# 8mu_pub.net
KiCad netlist of a schematic drawn in EAGLE
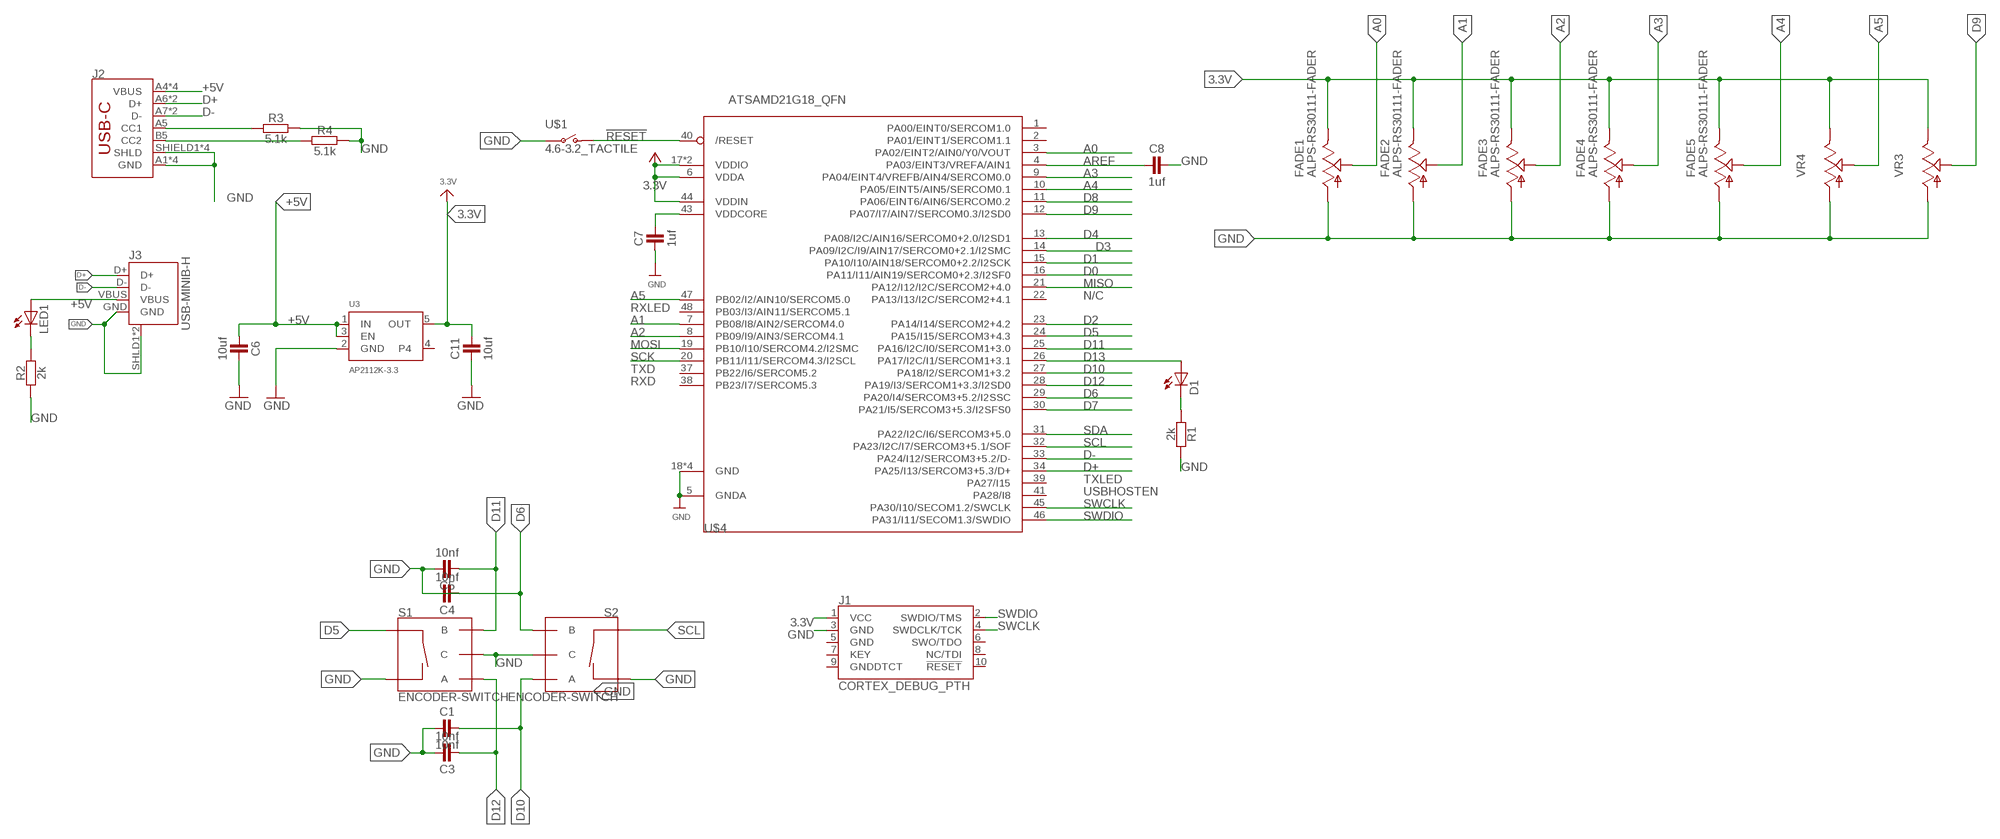
[diagram p0: schematic, sheet 1]

(export (version "E")
  (design (tool "Eeschema 10.0.6"))
  (components
    (comp (ref "C1")
      (value "10nf")
      (footprint "eagle-import:C0603")
      (libsource (lib "eagle-import") (part "CAPACITOR-0603"))
    )
    (comp (ref "C3")
      (value "10nf")
      (footprint "eagle-import:C0603")
      (libsource (lib "eagle-import") (part "CAPACITOR-0603"))
    )
    (comp (ref "C4")
      (value "10nf")
      (footprint "eagle-import:C0603")
      (libsource (lib "eagle-import") (part "CAPACITOR-0603"))
    )
    (comp (ref "C5")
      (value "10nf")
      (footprint "eagle-import:C0603")
      (libsource (lib "eagle-import") (part "CAPACITOR-0603"))
    )
    (comp (ref "C6")
      (value "10uf")
      (footprint "eagle-import:C0603")
      (libsource (lib "eagle-import") (part "CAPACITOR-0603"))
    )
    (comp (ref "C7")
      (value "1uf")
      (footprint "eagle-import:C0603")
      (libsource (lib "eagle-import") (part "CAPACITOR-0603"))
    )
    (comp (ref "C8")
      (value "1uf")
      (footprint "eagle-import:C0603")
      (libsource (lib "eagle-import") (part "CAPACITOR-0603"))
    )
    (comp (ref "C11")
      (value "10uf")
      (footprint "eagle-import:C0603")
      (libsource (lib "eagle-import") (part "CAPACITOR-0603"))
    )
    (comp (ref "D1")
      (value "LED3MM")
      (footprint "eagle-import:LED3MM")
      (libsource (lib "eagle-import") (part "LED3MM"))
    )
    (comp (ref "FADE1")
      (value "ALPS-RS30111-FADER")
      (footprint "eagle-import:ALPS-RS30111-FADER")
      (libsource (lib "eagle-import") (part "ALPS-RS30111-FADER"))
    )
    (comp (ref "FADE2")
      (value "ALPS-RS30111-FADER")
      (footprint "eagle-import:ALPS-RS30111-FADER")
      (libsource (lib "eagle-import") (part "ALPS-RS30111-FADER"))
    )
    (comp (ref "FADE3")
      (value "ALPS-RS30111-FADER")
      (footprint "eagle-import:ALPS-RS30111-FADER")
      (libsource (lib "eagle-import") (part "ALPS-RS30111-FADER"))
    )
    (comp (ref "FADE4")
      (value "ALPS-RS30111-FADER")
      (footprint "eagle-import:ALPS-RS30111-FADER")
      (libsource (lib "eagle-import") (part "ALPS-RS30111-FADER"))
    )
    (comp (ref "FADE5")
      (value "ALPS-RS30111-FADER")
      (footprint "eagle-import:ALPS-RS30111-FADER")
      (libsource (lib "eagle-import") (part "ALPS-RS30111-FADER"))
    )
    (comp (ref "J1")
      (value "CORTEX_DEBUG_PTH")
      (footprint "eagle-import:2X5-PTH-1.27MM")
      (libsource (lib "eagle-import") (part "CORTEX_DEBUG_PTH"))
    )
    (comp (ref "J2")
      (value "USB_C")
      (footprint "eagle-import:CX90M-16P-USB-C-MIDMOUNT")
      (libsource (lib "eagle-import") (part "USB_C"))
    )
    (comp (ref "J3")
      (value "USB-MINIB-H")
      (footprint "eagle-import:USB-MINIB-H")
      (libsource (lib "eagle-import") (part "USB-MINIB-H"))
    )
    (comp (ref "LED1")
      (value "LED3MM")
      (footprint "eagle-import:LED3MM")
      (libsource (lib "eagle-import") (part "LED3MM"))
    )
    (comp (ref "R1")
      (value "2k")
      (footprint "eagle-import:C0603")
      (libsource (lib "eagle-import") (part "RESISTOR-0603"))
    )
    (comp (ref "R2")
      (value "2k")
      (footprint "eagle-import:C0603")
      (libsource (lib "eagle-import") (part "RESISTOR-0603"))
    )
    (comp (ref "R3")
      (value "5.1k")
      (footprint "eagle-import:C0603")
      (libsource (lib "eagle-import") (part "RESISTOR-0603"))
    )
    (comp (ref "R4")
      (value "5.1k")
      (footprint "eagle-import:C0603")
      (libsource (lib "eagle-import") (part "RESISTOR-0603"))
    )
    (comp (ref "S1")
      (value "ENCODER-SWITCH")
      (footprint "eagle-import:ROTARY_ENC_PLAIN")
      (libsource (lib "eagle-import") (part "ENCODER-SWITCH"))
    )
    (comp (ref "S2")
      (value "ENCODER-SWITCH")
      (footprint "eagle-import:ROTARY_ENC_PLAIN")
      (libsource (lib "eagle-import") (part "ENCODER-SWITCH"))
    )
    (comp (ref "U$1")
      (value "4.6-3.2_TACTILE")
      (footprint "eagle-import:TACTILE_SWITCH_SMD_4.6X2.8MM")
      (libsource (lib "eagle-import") (part "4.6-3.2_TACTILE"))
    )
    (comp (ref "U$4")
      (value "ATSAMD21G18_QFN")
      (footprint "eagle-import:TQFN48_7MM")
      (libsource (lib "eagle-import") (part "ATSAMD21J_QFN"))
    )
    (comp (ref "U3")
      (value "AP2112K-3.3")
      (footprint "eagle-import:SOT23-5")
      (libsource (lib "eagle-import") (part "VREG_SOT23-5"))
    )
    (comp (ref "VR3")
      (value "9MM_SNAP-IN_POT_")
      (footprint "eagle-import:9MM_SNAP-IN_POT")
      (libsource (lib "eagle-import") (part "9MM_SNAP-IN_POT_"))
    )
    (comp (ref "VR4")
      (value "9MM_SNAP-IN_POT_")
      (footprint "eagle-import:9MM_SNAP-IN_POT")
      (libsource (lib "eagle-import") (part "9MM_SNAP-IN_POT_"))
    )
  )
  (nets
    (net (code "1") (name "+5V") (class "Default")
      (node (ref "C6") (pin "1") (pinfunction "1_1") (pintype "passive"))
      (node (ref "J2") (pin "A4") (pinfunction "VBUS_A4") (pintype "bidirectional"))
      (node (ref "J2") (pin "A9") (pinfunction "VBUS_A9") (pintype "bidirectional"))
      (node (ref "J2") (pin "B4") (pinfunction "VBUS_B4") (pintype "bidirectional"))
      (node (ref "J2") (pin "B9") (pinfunction "VBUS_B9") (pintype "bidirectional"))
      (node (ref "J3") (pin "VBUS") (pinfunction "VBUS_VBUS") (pintype "power_in"))
      (node (ref "LED1") (pin "A") (pinfunction "A_A") (pintype "passive"))
      (node (ref "U3") (pin "1") (pinfunction "IN_1") (pintype "bidirectional"))
      (node (ref "U3") (pin "3") (pinfunction "EN_3") (pintype "bidirectional"))
    )
    (net (code "2") (name "/AREF") (class "Default")
      (node (ref "C8") (pin "1") (pinfunction "1_1") (pintype "passive"))
      (node (ref "U$4") (pin "4") (pinfunction "PA03/EINT3/VREFA/AIN1_4") (pintype "bidirectional"))
    )
    (net (code "3") (name "/D0") (class "Default")
      (node (ref "U$4") (pin "16") (pinfunction "PA11/I11/AIN19/SERCOM0+2.3/I2SF0_16") (pintype "bidirectional"))
    )
    (net (code "4") (name "/D1") (class "Default")
      (node (ref "U$4") (pin "15") (pinfunction "PA10/I10/AIN18/SERCOM0+2.2/I2SCK_15") (pintype "bidirectional"))
    )
    (net (code "5") (name "/D2") (class "Default")
      (node (ref "U$4") (pin "23") (pinfunction "PA14/I14/SERCOM2+4.2_23") (pintype "bidirectional"))
    )
    (net (code "6") (name "/D3") (class "Default")
      (node (ref "U$4") (pin "14") (pinfunction "PA09/I2C/I9/AIN17/SERCOM0+2.1/I2SMC_14") (pintype "bidirectional"))
    )
    (net (code "7") (name "/D4") (class "Default")
      (node (ref "U$4") (pin "13") (pinfunction "PA08/I2C/AIN16/SERCOM0+2.0/I2SD1_13") (pintype "bidirectional"))
    )
    (net (code "8") (name "/D7") (class "Default")
      (node (ref "U$4") (pin "30") (pinfunction "PA21/I5/SERCOM3+5.3/I2SFS0_30") (pintype "bidirectional"))
    )
    (net (code "9") (name "/D8") (class "Default")
      (node (ref "U$4") (pin "11") (pinfunction "PA06/EINT6/AIN6/SERCOM0.2_11") (pintype "bidirectional"))
    )
    (net (code "10") (name "/D13") (class "Default")
      (node (ref "D1") (pin "A") (pinfunction "A_A") (pintype "passive"))
      (node (ref "U$4") (pin "26") (pinfunction "PA17/I2C/I1/SERCOM1+3.1_26") (pintype "bidirectional"))
    )
    (net (code "11") (name "/MISO") (class "Default")
      (node (ref "U$4") (pin "21") (pinfunction "PA12/I12/I2C/SERCOM2+4.0_21") (pintype "bidirectional"))
    )
    (net (code "12") (name "/MOSI") (class "Default")
      (node (ref "U$4") (pin "19") (pinfunction "PB10/I10/SERCOM4.2/I2SMC_19") (pintype "bidirectional"))
    )
    (net (code "13") (name "/SCK") (class "Default")
      (node (ref "U$4") (pin "20") (pinfunction "PB11/I11/SERCOM4.3/I2SCL_20") (pintype "bidirectional"))
    )
    (net (code "14") (name "/SDA") (class "Default")
      (node (ref "U$4") (pin "31") (pinfunction "PA22/I2C/I6/SERCOM3+5.0_31") (pintype "bidirectional"))
    )
    (net (code "15") (name "/SWCLK") (class "Default")
      (node (ref "J1") (pin "4") (pinfunction "SWDCLK/TCK_4") (pintype "bidirectional"))
      (node (ref "U$4") (pin "45") (pinfunction "PA30/I10/SECOM1.2/SWCLK_45") (pintype "bidirectional"))
    )
    (net (code "16") (name "/SWDIO") (class "Default")
      (node (ref "J1") (pin "2") (pinfunction "SWDIO/TMS_2") (pintype "bidirectional"))
      (node (ref "U$4") (pin "46") (pinfunction "PA31/I11/SECOM1.3/SWDIO_46") (pintype "bidirectional"))
    )
    (net (code "17") (name "/~{RESET}") (class "Default")
      (node (ref "U$1") (pin "3") (pinfunction "O_3") (pintype "passive"))
      (node (ref "U$1") (pin "4") (pinfunction "O_4") (pintype "passive"))
      (node (ref "U$4") (pin "40") (pinfunction "/RESET_40") (pintype "bidirectional"))
    )
    (net (code "18") (name "3.3V") (class "Default")
      (node (ref "C11") (pin "2") (pinfunction "2_2") (pintype "passive"))
      (node (ref "FADE1") (pin "3") (pinfunction "E_3") (pintype "passive"))
      (node (ref "FADE2") (pin "3") (pinfunction "E_3") (pintype "passive"))
      (node (ref "FADE3") (pin "3") (pinfunction "E_3") (pintype "passive"))
      (node (ref "FADE4") (pin "3") (pinfunction "E_3") (pintype "passive"))
      (node (ref "FADE5") (pin "3") (pinfunction "E_3") (pintype "passive"))
      (node (ref "J1") (pin "1") (pinfunction "VCC_1") (pintype "bidirectional"))
      (node (ref "U$4") (pin "17") (pinfunction "VDDIO_17") (pintype "power_in"))
      (node (ref "U$4") (pin "36") (pinfunction "VDDIO_36") (pintype "power_in"))
      (node (ref "U$4") (pin "44") (pinfunction "VDDIN_44") (pintype "power_in"))
      (node (ref "U$4") (pin "6") (pinfunction "VDDA_6") (pintype "power_in"))
      (node (ref "U3") (pin "5") (pinfunction "OUT_5") (pintype "bidirectional"))
      (node (ref "VR3") (pin "3") (pinfunction "E_3") (pintype "passive"))
      (node (ref "VR4") (pin "3") (pinfunction "E_3") (pintype "passive"))
    )
    (net (code "19") (name "A0") (class "Default")
      (node (ref "FADE1") (pin "2") (pinfunction "S_2") (pintype "passive"))
      (node (ref "U$4") (pin "3") (pinfunction "PA02/EINT2/AIN0/Y0/VOUT_3") (pintype "bidirectional"))
    )
    (net (code "20") (name "A1") (class "Default")
      (node (ref "FADE2") (pin "2") (pinfunction "S_2") (pintype "passive"))
      (node (ref "U$4") (pin "7") (pinfunction "PB08/I8/AIN2/SERCOM4.0_7") (pintype "bidirectional"))
    )
    (net (code "21") (name "A2") (class "Default")
      (node (ref "FADE3") (pin "2") (pinfunction "S_2") (pintype "passive"))
      (node (ref "U$4") (pin "8") (pinfunction "PB09/I9/AIN3/SERCOM4.1_8") (pintype "bidirectional"))
    )
    (net (code "22") (name "A3") (class "Default")
      (node (ref "FADE4") (pin "2") (pinfunction "S_2") (pintype "passive"))
      (node (ref "U$4") (pin "9") (pinfunction "PA04/EINT4/VREFB/AIN4/SERCOM0.0_9") (pintype "bidirectional"))
    )
    (net (code "23") (name "A4") (class "Default")
      (node (ref "FADE5") (pin "2") (pinfunction "S_2") (pintype "passive"))
      (node (ref "U$4") (pin "10") (pinfunction "PA05/EINT5/AIN5/SERCOM0.1_10") (pintype "bidirectional"))
    )
    (net (code "24") (name "A5") (class "Default")
      (node (ref "U$4") (pin "47") (pinfunction "PB02/I2/AIN10/SERCOM5.0_47") (pintype "bidirectional"))
      (node (ref "VR4") (pin "2") (pinfunction "S_2") (pintype "passive"))
    )
    (net (code "25") (name "D+") (class "Default")
      (node (ref "J2") (pin "A6") (pinfunction "D+_A6") (pintype "bidirectional"))
      (node (ref "J2") (pin "B6") (pinfunction "D+_B6") (pintype "bidirectional"))
      (node (ref "J3") (pin "D+") (pinfunction "D+_D+") (pintype "bidirectional"))
      (node (ref "U$4") (pin "34") (pinfunction "PA25/I13/SERCOM3+5.3/D+_34") (pintype "bidirectional"))
    )
    (net (code "26") (name "D-") (class "Default")
      (node (ref "J2") (pin "A7") (pinfunction "D-_A7") (pintype "bidirectional"))
      (node (ref "J2") (pin "B7") (pinfunction "D-_B7") (pintype "bidirectional"))
      (node (ref "J3") (pin "D-") (pinfunction "D-_D-") (pintype "bidirectional"))
      (node (ref "U$4") (pin "33") (pinfunction "PA24/I12/SERCOM3+5.2/D-_33") (pintype "bidirectional"))
    )
    (net (code "27") (name "D5") (class "Default")
      (node (ref "S1") (pin "SW+") (pinfunction "SW+_SW+") (pintype "bidirectional"))
      (node (ref "U$4") (pin "24") (pinfunction "PA15/I15/SERCOM3+4.3_24") (pintype "bidirectional"))
    )
    (net (code "28") (name "D6") (class "Default")
      (node (ref "C4") (pin "2") (pinfunction "2_2") (pintype "passive"))
      (node (ref "S2") (pin "B") (pinfunction "B_B") (pintype "bidirectional"))
      (node (ref "U$4") (pin "29") (pinfunction "PA20/I4/SERCOM3+5.2/I2SSC_29") (pintype "bidirectional"))
    )
    (net (code "29") (name "D9") (class "Default")
      (node (ref "U$4") (pin "12") (pinfunction "PA07/I7/AIN7/SERCOM0.3/I2SD0_12") (pintype "bidirectional"))
      (node (ref "VR3") (pin "2") (pinfunction "S_2") (pintype "passive"))
    )
    (net (code "30") (name "D10") (class "Default")
      (node (ref "C1") (pin "2") (pinfunction "2_2") (pintype "passive"))
      (node (ref "S2") (pin "A") (pinfunction "A_A") (pintype "bidirectional"))
      (node (ref "U$4") (pin "27") (pinfunction "PA18/I2/SERCOM1+3.2_27") (pintype "bidirectional"))
    )
    (net (code "31") (name "D11") (class "Default")
      (node (ref "C5") (pin "1") (pinfunction "1_1") (pintype "passive"))
      (node (ref "S1") (pin "B") (pinfunction "B_B") (pintype "bidirectional"))
      (node (ref "U$4") (pin "25") (pinfunction "PA16/I2C/I0/SERCOM1+3.0_25") (pintype "bidirectional"))
    )
    (net (code "32") (name "D12") (class "Default")
      (node (ref "C3") (pin "1") (pinfunction "1_1") (pintype "passive"))
      (node (ref "S1") (pin "A") (pinfunction "A_A") (pintype "bidirectional"))
      (node (ref "U$4") (pin "28") (pinfunction "PA19/I3/SERCOM1+3.3/I2SD0_28") (pintype "bidirectional"))
    )
    (net (code "33") (name "GND") (class "Default")
      (node (ref "C1") (pin "1") (pinfunction "1_1") (pintype "passive"))
      (node (ref "C11") (pin "1") (pinfunction "1_1") (pintype "passive"))
      (node (ref "C3") (pin "2") (pinfunction "2_2") (pintype "passive"))
      (node (ref "C4") (pin "1") (pinfunction "1_1") (pintype "passive"))
      (node (ref "C5") (pin "2") (pinfunction "2_2") (pintype "passive"))
      (node (ref "C6") (pin "2") (pinfunction "2_2") (pintype "passive"))
      (node (ref "C7") (pin "1") (pinfunction "1_1") (pintype "passive"))
      (node (ref "C8") (pin "2") (pinfunction "2_2") (pintype "passive"))
      (node (ref "FADE1") (pin "1") (pinfunction "A_1") (pintype "passive"))
      (node (ref "FADE2") (pin "1") (pinfunction "A_1") (pintype "passive"))
      (node (ref "FADE3") (pin "1") (pinfunction "A_1") (pintype "passive"))
      (node (ref "FADE4") (pin "1") (pinfunction "A_1") (pintype "passive"))
      (node (ref "FADE5") (pin "1") (pinfunction "A_1") (pintype "passive"))
      (node (ref "J1") (pin "3") (pinfunction "GND_3") (pintype "bidirectional"))
      (node (ref "J2") (pin "A1") (pinfunction "GND_A1") (pintype "bidirectional"))
      (node (ref "J2") (pin "A12") (pinfunction "GND_A12") (pintype "bidirectional"))
      (node (ref "J2") (pin "B1") (pinfunction "GND_B1") (pintype "bidirectional"))
      (node (ref "J2") (pin "B12") (pinfunction "GND_B12") (pintype "bidirectional"))
      (node (ref "J2") (pin "SHIELD1") (pinfunction "SHLD_SHIELD1") (pintype "bidirectional"))
      (node (ref "J2") (pin "SHIELD2") (pinfunction "SHLD_SHIELD2") (pintype "bidirectional"))
      (node (ref "J2") (pin "SHIELD3") (pinfunction "SHLD_SHIELD3") (pintype "bidirectional"))
      (node (ref "J2") (pin "SHIELD4") (pinfunction "SHLD_SHIELD4") (pintype "bidirectional"))
      (node (ref "J3") (pin "GND") (pinfunction "GND_GND") (pintype "power_in"))
      (node (ref "J3") (pin "SHLD1") (pinfunction "SHIELD_SHLD1") (pintype "passive"))
      (node (ref "J3") (pin "SHLD2") (pinfunction "SHIELD_SHLD2") (pintype "passive"))
      (node (ref "R1") (pin "2") (pinfunction "2_2") (pintype "passive"))
      (node (ref "R2") (pin "1") (pinfunction "1_1") (pintype "passive"))
      (node (ref "R3") (pin "2") (pinfunction "2_2") (pintype "passive"))
      (node (ref "R4") (pin "2") (pinfunction "2_2") (pintype "passive"))
      (node (ref "S1") (pin "C") (pinfunction "C_C") (pintype "bidirectional"))
      (node (ref "S1") (pin "SW-") (pinfunction "SW-_SW-") (pintype "bidirectional"))
      (node (ref "S2") (pin "C") (pinfunction "C_C") (pintype "bidirectional"))
      (node (ref "S2") (pin "SW-") (pinfunction "SW-_SW-") (pintype "bidirectional"))
      (node (ref "U$1") (pin "1") (pinfunction "P_1") (pintype "passive"))
      (node (ref "U$1") (pin "2") (pinfunction "P_2") (pintype "passive"))
      (node (ref "U$4") (pin "18") (pinfunction "GND_18") (pintype "power_in"))
      (node (ref "U$4") (pin "35") (pinfunction "GND_35") (pintype "power_in"))
      (node (ref "U$4") (pin "42") (pinfunction "GND_42") (pintype "power_in"))
      (node (ref "U$4") (pin "5") (pinfunction "GNDA_5") (pintype "power_in"))
      (node (ref "U$4") (pin "THERMAL") (pinfunction "GND_THERMAL") (pintype "power_in"))
      (node (ref "U3") (pin "2") (pinfunction "GND_2") (pintype "bidirectional"))
      (node (ref "VR3") (pin "1") (pinfunction "A_1") (pintype "passive"))
      (node (ref "VR4") (pin "1") (pinfunction "A_1") (pintype "passive"))
    )
    (net (code "34") (name "Net-(D1-C)") (class "Default")
      (node (ref "D1") (pin "K") (pinfunction "C_K") (pintype "passive"))
      (node (ref "R1") (pin "1") (pinfunction "1_1") (pintype "passive"))
    )
    (net (code "35") (name "Net-(J2-CC1)") (class "Default")
      (node (ref "J2") (pin "A5") (pinfunction "CC1_A5") (pintype "bidirectional"))
      (node (ref "R3") (pin "1") (pinfunction "1_1") (pintype "passive"))
    )
    (net (code "36") (name "Net-(J2-CC2)") (class "Default")
      (node (ref "J2") (pin "B5") (pinfunction "CC2_B5") (pintype "bidirectional"))
      (node (ref "R4") (pin "1") (pinfunction "1_1") (pintype "passive"))
    )
    (net (code "37") (name "Net-(LED1-C)") (class "Default")
      (node (ref "LED1") (pin "K") (pinfunction "C_K") (pintype "passive"))
      (node (ref "R2") (pin "2") (pinfunction "2_2") (pintype "passive"))
    )
    (net (code "38") (name "Net-(U$4-VDDCORE)") (class "Default")
      (node (ref "C7") (pin "2") (pinfunction "2_2") (pintype "passive"))
      (node (ref "U$4") (pin "43") (pinfunction "VDDCORE_43") (pintype "power_in"))
    )
    (net (code "39") (name "SCL") (class "Default")
      (node (ref "S2") (pin "SW+") (pinfunction "SW+_SW+") (pintype "bidirectional"))
      (node (ref "U$4") (pin "32") (pinfunction "PA23/I2C/I7/SERCOM3+5.1/SOF_32") (pintype "bidirectional"))
    )
    (net (code "40") (name "unconnected-(J1-GND-Pad5)") (class "Default")
      (node (ref "J1") (pin "5") (pinfunction "GND_5") (pintype "bidirectional"))
    )
    (net (code "41") (name "unconnected-(J1-GNDDTCT-Pad9)") (class "Default")
      (node (ref "J1") (pin "9") (pinfunction "GNDDTCT_9") (pintype "bidirectional"))
    )
    (net (code "42") (name "unconnected-(J1-KEY-Pad7)") (class "Default")
      (node (ref "J1") (pin "7") (pinfunction "KEY_7") (pintype "bidirectional"))
    )
    (net (code "43") (name "unconnected-(J1-NC{slash}TDI-Pad8)") (class "Default")
      (node (ref "J1") (pin "8") (pinfunction "NC/TDI_8") (pintype "bidirectional"))
    )
    (net (code "44") (name "unconnected-(J1-SWO{slash}TDO-Pad6)") (class "Default")
      (node (ref "J1") (pin "6") (pinfunction "SWO/TDO_6") (pintype "bidirectional"))
    )
    (net (code "45") (name "unconnected-(J1-~{RESET}-Pad10)") (class "Default")
      (node (ref "J1") (pin "10") (pinfunction "~{RESET}_10") (pintype "bidirectional"))
    )
    (net (code "46") (name "unconnected-(U$4-PA00{slash}EINT0{slash}SERCOM1.0-Pad1)") (class "Default")
      (node (ref "U$4") (pin "1") (pinfunction "PA00/EINT0/SERCOM1.0_1") (pintype "bidirectional"))
    )
    (net (code "47") (name "unconnected-(U$4-PA01{slash}EINT1{slash}SERCOM1.1-Pad2)") (class "Default")
      (node (ref "U$4") (pin "2") (pinfunction "PA01/EINT1/SERCOM1.1_2") (pintype "bidirectional"))
    )
    (net (code "48") (name "unconnected-(U$4-PA13{slash}I13{slash}I2C{slash}SERCOM2+4.1-Pad22)") (class "Default")
      (node (ref "U$4") (pin "22") (pinfunction "PA13/I13/I2C/SERCOM2+4.1_22") (pintype "bidirectional"))
    )
    (net (code "49") (name "unconnected-(U$4-PA27{slash}I15-Pad39)") (class "Default")
      (node (ref "U$4") (pin "39") (pinfunction "PA27/I15_39") (pintype "bidirectional"))
    )
    (net (code "50") (name "unconnected-(U$4-PA28{slash}I8-Pad41)") (class "Default")
      (node (ref "U$4") (pin "41") (pinfunction "PA28/I8_41") (pintype "bidirectional"))
    )
    (net (code "51") (name "unconnected-(U$4-PB03{slash}I3{slash}AIN11{slash}SERCOM5.1-Pad48)") (class "Default")
      (node (ref "U$4") (pin "48") (pinfunction "PB03/I3/AIN11/SERCOM5.1_48") (pintype "bidirectional"))
    )
    (net (code "52") (name "unconnected-(U$4-PB22{slash}I6{slash}SERCOM5.2-Pad37)") (class "Default")
      (node (ref "U$4") (pin "37") (pinfunction "PB22/I6/SERCOM5.2_37") (pintype "bidirectional"))
    )
    (net (code "53") (name "unconnected-(U$4-PB23{slash}I7{slash}SERCOM5.3-Pad38)") (class "Default")
      (node (ref "U$4") (pin "38") (pinfunction "PB23/I7/SERCOM5.3_38") (pintype "bidirectional"))
    )
    (net (code "54") (name "unconnected-(U3-P4-Pad4)") (class "Default")
      (node (ref "U3") (pin "4") (pinfunction "P4_4") (pintype "bidirectional"))
    )
  )
)
